# Adafruit_Metro_M0_Express.net
KiCad netlist of a schematic drawn in EAGLE
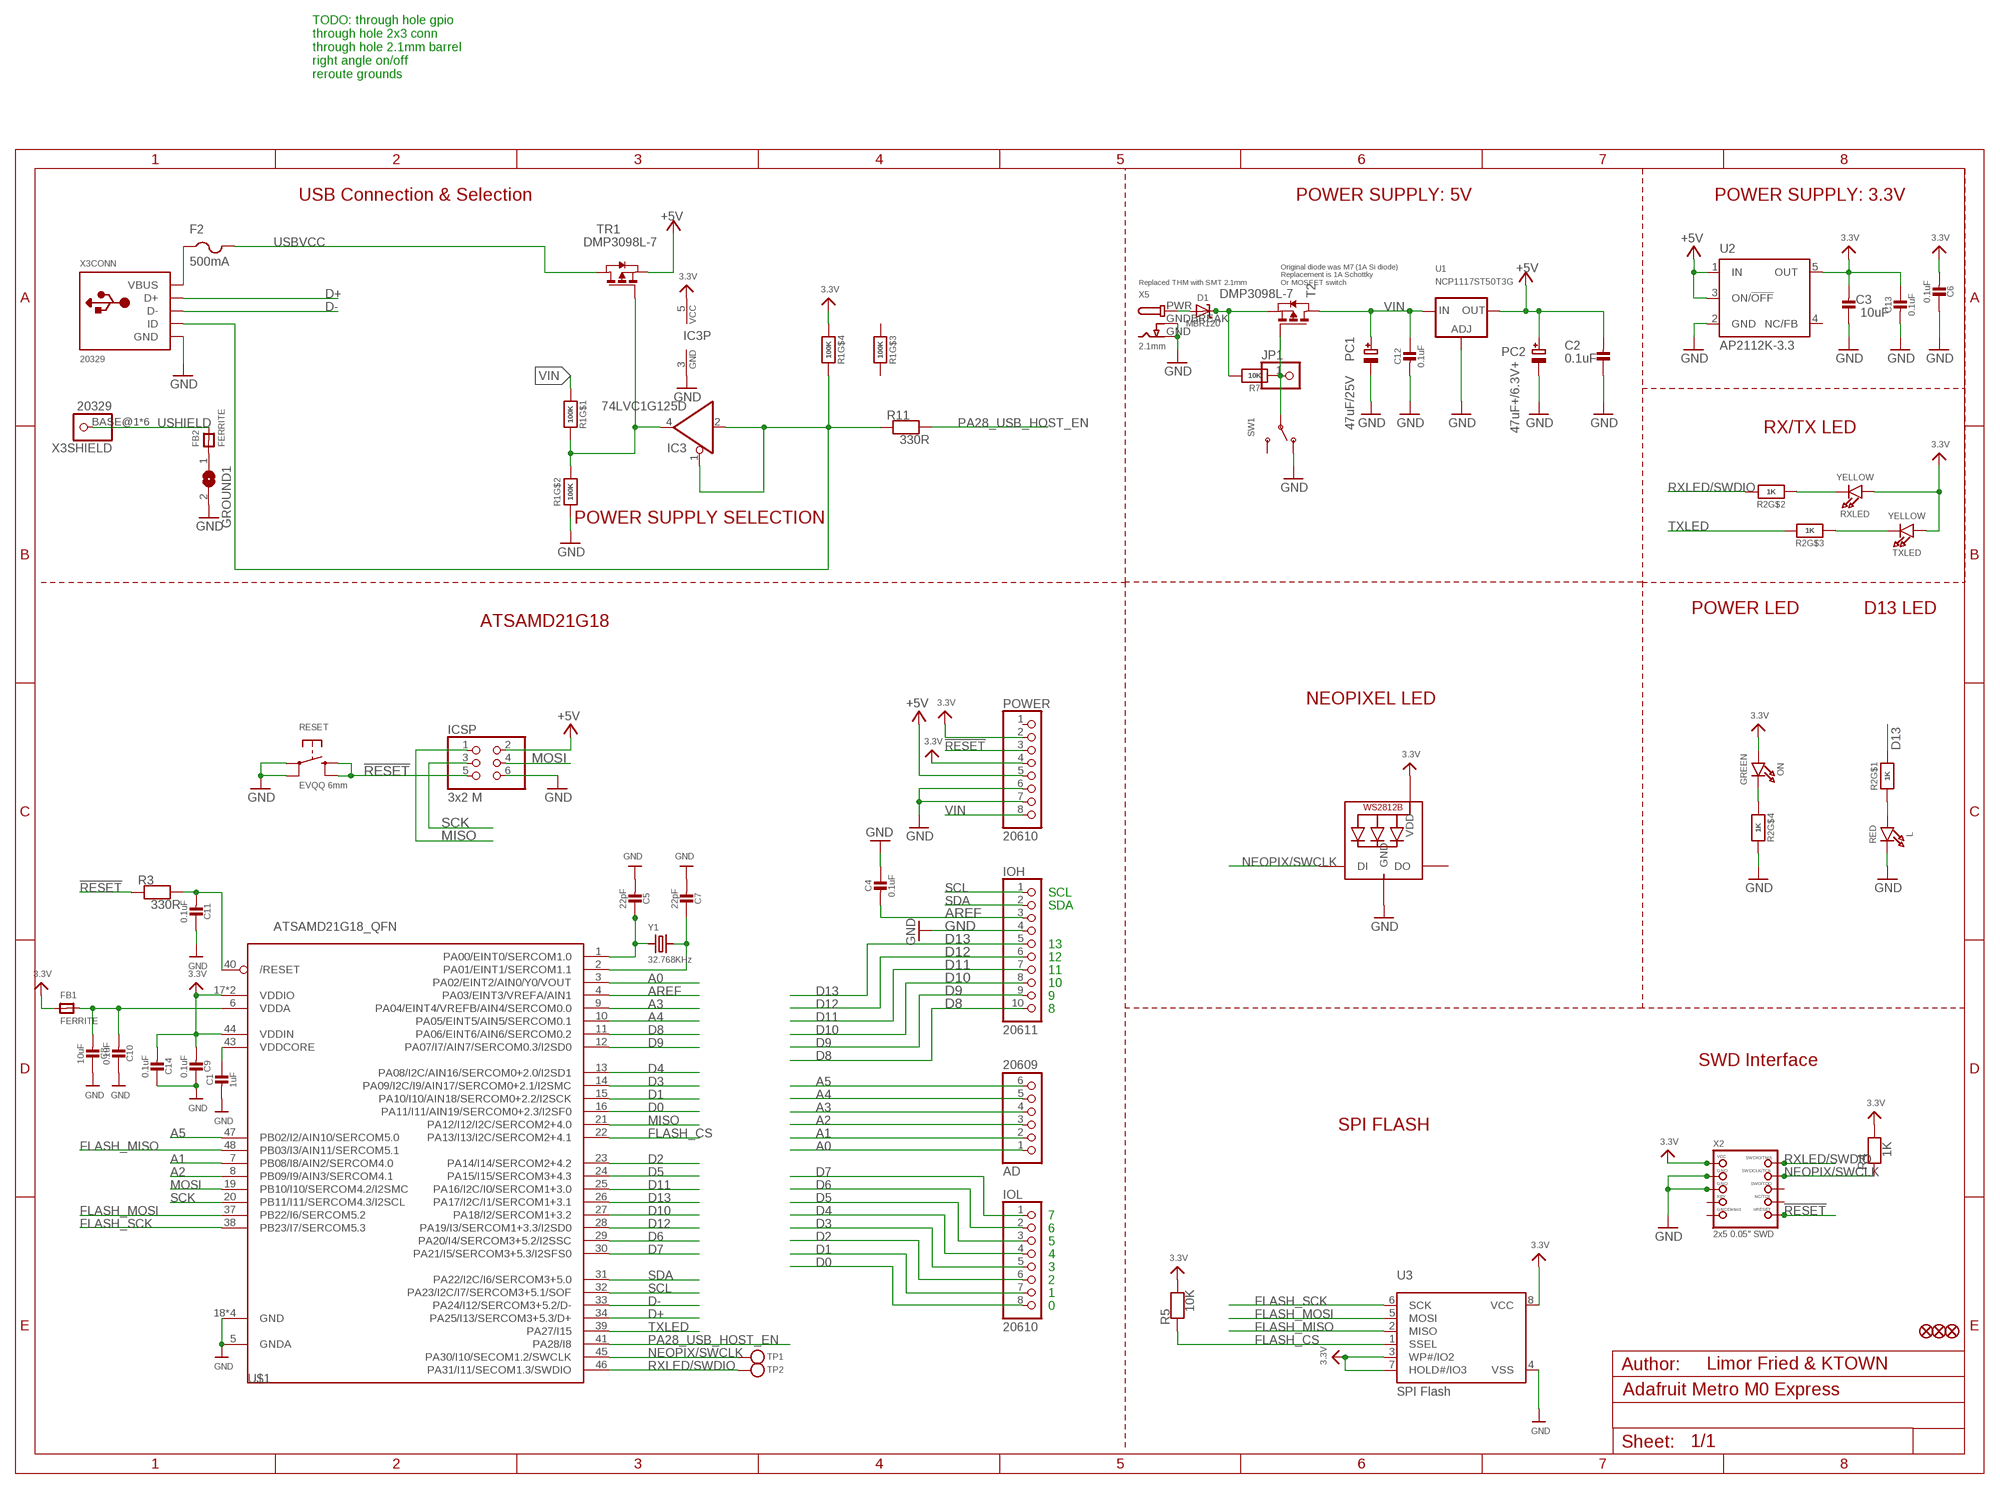
[diagram p0: schematic, sheet 1]

(export (version "E")
  (design (tool "Eeschema 10.0.6"))
  (components
    (comp (ref "AD")
      (value "20609")
      (footprint "eagle-import:1X06_OVALWAVE")
      (libsource (lib "eagle-import") (part "HEADER-1X6OVALWAVE"))
    )
    (comp (ref "C1")
      (value "1uF")
      (footprint "eagle-import:0805-NO")
      (libsource (lib "eagle-import") (part "CAP_CERAMIC0805-NOOUTLINE"))
    )
    (comp (ref "C2")
      (value "0.1uF")
      (footprint "eagle-import:0805-NO")
      (libsource (lib "eagle-import") (part "CAP_CERAMIC0805-NOOUTLINE"))
    )
    (comp (ref "C3")
      (value "10uF")
      (footprint "eagle-import:0805-NO")
      (libsource (lib "eagle-import") (part "CAP_CERAMIC0805-NOOUTLINE"))
    )
    (comp (ref "C4")
      (value "0.1uF")
      (footprint "eagle-import:0805-NO")
      (libsource (lib "eagle-import") (part "CAP_CERAMIC0805-NOOUTLINE"))
    )
    (comp (ref "C5")
      (value "22pF")
      (footprint "eagle-import:0805-NO")
      (libsource (lib "eagle-import") (part "CAP_CERAMIC0805-NOOUTLINE"))
    )
    (comp (ref "C6")
      (value "0.1uF")
      (footprint "eagle-import:0805-NO")
      (libsource (lib "eagle-import") (part "CAP_CERAMIC0805-NOOUTLINE"))
    )
    (comp (ref "C7")
      (value "22pF")
      (footprint "eagle-import:0805-NO")
      (libsource (lib "eagle-import") (part "CAP_CERAMIC0805-NOOUTLINE"))
    )
    (comp (ref "C8")
      (value "10uF")
      (footprint "eagle-import:0805-NO")
      (libsource (lib "eagle-import") (part "CAP_CERAMIC0805-NOOUTLINE"))
    )
    (comp (ref "C9")
      (value "0.1uF")
      (footprint "eagle-import:0805-NO")
      (libsource (lib "eagle-import") (part "CAP_CERAMIC0805-NOOUTLINE"))
    )
    (comp (ref "C10")
      (value "0.1uF")
      (footprint "eagle-import:0805-NO")
      (libsource (lib "eagle-import") (part "CAP_CERAMIC0805-NOOUTLINE"))
    )
    (comp (ref "C11")
      (value "0.1uF")
      (footprint "eagle-import:0805-NO")
      (libsource (lib "eagle-import") (part "CAP_CERAMIC0805-NOOUTLINE"))
    )
    (comp (ref "C12")
      (value "0.1uF")
      (footprint "eagle-import:0805-NO")
      (libsource (lib "eagle-import") (part "CAP_CERAMIC0805-NOOUTLINE"))
    )
    (comp (ref "C13")
      (value "0.1uF")
      (footprint "eagle-import:0805-NO")
      (libsource (lib "eagle-import") (part "CAP_CERAMIC0805-NOOUTLINE"))
    )
    (comp (ref "C14")
      (value "0.1uF")
      (footprint "eagle-import:0805-NO")
      (libsource (lib "eagle-import") (part "CAP_CERAMIC0805-NOOUTLINE"))
    )
    (comp (ref "D1")
      (value "MBR120")
      (footprint "eagle-import:SOD-123")
      (libsource (lib "eagle-import") (part "DIODE-SCHOTTKYSOD-123"))
    )
    (comp (ref "F2")
      (value "500mA")
      (footprint "eagle-import:R1206")
      (libsource (lib "eagle-import") (part "PTCFUSE-1206"))
    )
    (comp (ref "FB1")
      (value "FERRITE")
      (footprint "eagle-import:0805-NO")
      (libsource (lib "eagle-import") (part "FERRITE-0805NO"))
    )
    (comp (ref "FB2")
      (value "FERRITE")
      (footprint "eagle-import:0805-NO")
      (libsource (lib "eagle-import") (part "FERRITE-0805NO"))
    )
    (comp (ref "FD1")
      (value "FIDUCIAL_1MM")
      (footprint "eagle-import:FIDUCIAL_1MM")
      (libsource (lib "eagle-import") (part "FIDUCIAL_1MM"))
    )
    (comp (ref "FD2")
      (value "FIDUCIAL_1MM")
      (footprint "eagle-import:FIDUCIAL_1MM")
      (libsource (lib "eagle-import") (part "FIDUCIAL_1MM"))
    )
    (comp (ref "FD3")
      (value "FIDUCIAL_1MM")
      (footprint "eagle-import:FIDUCIAL_1MM")
      (libsource (lib "eagle-import") (part "FIDUCIAL_1MM"))
    )
    (comp (ref "GROUND1")
      (value "SJ")
      (footprint "eagle-import:SJ")
      (libsource (lib "eagle-import") (part "SJ"))
    )
    (comp (ref "IC3")
      (value "74LVC1G125D")
      (footprint "eagle-import:SOT23-5")
      (libsource (lib "eagle-import") (part "741G125DBVAHC"))
    )
    (comp (ref "ICSP")
      (value "3x2 M")
      (footprint "eagle-import:2X03_ROUND_70MIL")
      (libsource (lib "eagle-import") (part "HEADER-2X3"))
    )
    (comp (ref "IOH")
      (value "20611")
      (footprint "eagle-import:1X10_OVALWAVE")
      (libsource (lib "eagle-import") (part "HEADER-1X10OVALWAVE"))
    )
    (comp (ref "IOL")
      (value "20610")
      (footprint "eagle-import:1X08_OVALWAVE")
      (libsource (lib "eagle-import") (part "HEADER-1X8OVALWAVE"))
    )
    (comp (ref "JP1")
      (value "HEADER-1X1ROUND")
      (footprint "eagle-import:1X01_ROUND")
      (libsource (lib "eagle-import") (part "HEADER-1X1ROUND"))
    )
    (comp (ref "L")
      (value "RED")
      (footprint "eagle-import:CHIPLED_0805_NOOUTLINE")
      (libsource (lib "eagle-import") (part "LED0805_NOOUTLINE"))
    )
    (comp (ref "LED1")
      (value "WS2812B3535")
      (footprint "eagle-import:LED3535")
      (libsource (lib "eagle-import") (part "WS2812B3535"))
    )
    (comp (ref "ON")
      (value "GREEN")
      (footprint "eagle-import:CHIPLED_0805_NOOUTLINE")
      (libsource (lib "eagle-import") (part "LED0805_NOOUTLINE"))
    )
    (comp (ref "PC1")
      (value "47uF/25V")
      (footprint "eagle-import:PANASONIC_D")
      (libsource (lib "eagle-import") (part "CAP_ELECTROLYTICPANASONIC_D"))
    )
    (comp (ref "PC2")
      (value "47uF+/6.3V+")
      (footprint "eagle-import:PANASONIC_D")
      (libsource (lib "eagle-import") (part "CAP_ELECTROLYTICPANASONIC_D"))
    )
    (comp (ref "POWER")
      (value "20610")
      (footprint "eagle-import:1X08_OVALWAVE")
      (libsource (lib "eagle-import") (part "HEADER-1X8OVALWAVE"))
    )
    (comp (ref "R1")
      (value "100K")
      (footprint "eagle-import:RESPACK_4X0603")
      (libsource (lib "eagle-import") (part "RESISTOR_4PACK"))
    )
    (comp (ref "R2")
      (value "1K")
      (footprint "eagle-import:RESPACK_4X0603")
      (libsource (lib "eagle-import") (part "RESISTOR_4PACK"))
    )
    (comp (ref "R3")
      (value "330R")
      (footprint "eagle-import:0805-NO")
      (libsource (lib "eagle-import") (part "RESISTOR0805_NOOUTLINE"))
    )
    (comp (ref "R4")
      (value "1K")
      (footprint "eagle-import:0805-NO")
      (libsource (lib "eagle-import") (part "RESISTOR0805_NOOUTLINE"))
    )
    (comp (ref "R5")
      (value "10K")
      (footprint "eagle-import:0805-NO")
      (libsource (lib "eagle-import") (part "RESISTOR0805_NOOUTLINE"))
    )
    (comp (ref "R7")
      (value "10K")
      (footprint "eagle-import:0805-NO")
      (libsource (lib "eagle-import") (part "RESISTOR0805_NOOUTLINE"))
    )
    (comp (ref "R11")
      (value "330R")
      (footprint "eagle-import:0805-NO")
      (libsource (lib "eagle-import") (part "RESISTOR0805_NOOUTLINE"))
    )
    (comp (ref "RESET")
      (value "EVQQ 6mm")
      (footprint "eagle-import:EVQ-Q2")
      (libsource (lib "eagle-import") (part "SWITCH_TACT_SMT"))
    )
    (comp (ref "RXLED")
      (value "YELLOW")
      (footprint "eagle-import:CHIPLED_0805_NOOUTLINE")
      (libsource (lib "eagle-import") (part "LED0805_NOOUTLINE"))
    )
    (comp (ref "SW1")
      (value "SWITCH_SPDT")
      (footprint "eagle-import:SPDT_SMT_SSSS811101")
      (libsource (lib "eagle-import") (part "SWITCH_SPDT"))
    )
    (comp (ref "T2")
      (value "DMP3098L-7")
      (footprint "eagle-import:SOT-23")
      (libsource (lib "eagle-import") (part "PMOSSOT23"))
    )
    (comp (ref "TP1")
      (value "TESTPOINTROUND1.5MM")
      (footprint "eagle-import:TESTPOINT_ROUND_1.5MM")
      (libsource (lib "eagle-import") (part "TESTPOINTROUND1.5MM"))
    )
    (comp (ref "TP2")
      (value "TESTPOINTROUND1.5MM")
      (footprint "eagle-import:TESTPOINT_ROUND_1.5MM")
      (libsource (lib "eagle-import") (part "TESTPOINTROUND1.5MM"))
    )
    (comp (ref "TR1")
      (value "DMP3098L-7")
      (footprint "eagle-import:SOT-23")
      (fields (field (name "PART_NUMBER") "PMV48XP"))
      (libsource (lib "eagle-import") (part "0297_PMV48XP"))
    )
    (comp (ref "TXLED")
      (value "YELLOW")
      (footprint "eagle-import:CHIPLED_0805_NOOUTLINE")
      (libsource (lib "eagle-import") (part "LED0805_NOOUTLINE"))
    )
    (comp (ref "U$1")
      (value "ATSAMD21G18_QFN")
      (footprint "eagle-import:TQFN48_7MM")
      (libsource (lib "eagle-import") (part "ATSAMD21J_QFN"))
    )
    (comp (ref "U1")
      (value "NCP1117ST50T3G")
      (footprint "eagle-import:SOT223-R")
      (libsource (lib "eagle-import") (part "LM1117SOT223-REFLOW"))
    )
    (comp (ref "U2")
      (value "AP2112K-3.3")
      (footprint "eagle-import:SOT23-DBV")
      (libsource (lib "eagle-import") (part "LP2985-XXDBVR33"))
    )
    (comp (ref "U3")
      (value "SPI Flash")
      (footprint "eagle-import:SOIC8_208MIL")
      (libsource (lib "eagle-import") (part "SPIFLASH_SOIC8208MIL"))
    )
    (comp (ref "X2")
      (value "2x5 0.05\" SWD")
      (footprint "eagle-import:2X05_1.27MM_BOX_POSTS")
      (libsource (lib "eagle-import") (part "JTAG-CORTEXBOXPOSTS"))
    )
    (comp (ref "X3")
      (value "20329")
      (footprint "eagle-import:4UCONN_20329_V2")
      (libsource (lib "eagle-import") (part "USB_W_SHIELD_V2"))
    )
    (comp (ref "X5")
      (value "2.1mm")
      (footprint "eagle-import:DCJACK_2MM_PTH")
      (libsource (lib "eagle-import") (part "DCBARRELPTH"))
    )
    (comp (ref "Y1")
      (value "32.768KHz")
      (footprint "eagle-import:CRYSTAL_8X3.8")
      (libsource (lib "eagle-import") (part "CRYSTAL8.0X3.8"))
    )
  )
  (nets
    (net (code "1") (name "+5V") (class "Default")
      (node (ref "C2") (pin "2") (pinfunction "2_2") (pintype "passive"))
      (node (ref "ICSP") (pin "2") (pinfunction "2_2") (pintype "passive"))
      (node (ref "PC2") (pin "+") (pinfunction "+_+") (pintype "passive"))
      (node (ref "POWER") (pin "5") (pinfunction "5_5") (pintype "passive"))
      (node (ref "TR1") (pin "2") (pinfunction "S_2") (pintype "passive"))
      (node (ref "U1") (pin "2") (pinfunction "OUT_2") (pintype "passive"))
      (node (ref "U1") (pin "4") (pinfunction "OUT_4") (pintype "passive"))
      (node (ref "U2") (pin "1") (pinfunction "IN_1") (pintype "input"))
      (node (ref "U2") (pin "3") (pinfunction "ON/~{OFF}_3") (pintype "input"))
    )
    (net (code "2") (name "/A0") (class "Default")
      (node (ref "AD") (pin "1") (pinfunction "1_1") (pintype "passive"))
      (node (ref "U$1") (pin "3") (pinfunction "PA02/EINT2/AIN0/Y0/VOUT_3") (pintype "bidirectional"))
    )
    (net (code "3") (name "/A1") (class "Default")
      (node (ref "AD") (pin "2") (pinfunction "2_2") (pintype "passive"))
      (node (ref "U$1") (pin "7") (pinfunction "PB08/I8/AIN2/SERCOM4.0_7") (pintype "bidirectional"))
    )
    (net (code "4") (name "/A2") (class "Default")
      (node (ref "AD") (pin "3") (pinfunction "3_3") (pintype "passive"))
      (node (ref "U$1") (pin "8") (pinfunction "PB09/I9/AIN3/SERCOM4.1_8") (pintype "bidirectional"))
    )
    (net (code "5") (name "/A3") (class "Default")
      (node (ref "AD") (pin "4") (pinfunction "4_4") (pintype "passive"))
      (node (ref "U$1") (pin "9") (pinfunction "PA04/EINT4/VREFB/AIN4/SERCOM0.0_9") (pintype "bidirectional"))
    )
    (net (code "6") (name "/A4") (class "Default")
      (node (ref "AD") (pin "5") (pinfunction "5_5") (pintype "passive"))
      (node (ref "U$1") (pin "10") (pinfunction "PA05/EINT5/AIN5/SERCOM0.1_10") (pintype "bidirectional"))
    )
    (net (code "7") (name "/A5") (class "Default")
      (node (ref "AD") (pin "6") (pinfunction "6_6") (pintype "passive"))
      (node (ref "U$1") (pin "47") (pinfunction "PB02/I2/AIN10/SERCOM5.0_47") (pintype "bidirectional"))
    )
    (net (code "8") (name "/AREF") (class "Default")
      (node (ref "C4") (pin "2") (pinfunction "2_2") (pintype "passive"))
      (node (ref "IOH") (pin "3") (pinfunction "3_3") (pintype "passive"))
      (node (ref "U$1") (pin "4") (pinfunction "PA03/EINT3/VREFA/AIN1_4") (pintype "bidirectional"))
    )
    (net (code "9") (name "/D+") (class "Default")
      (node (ref "U$1") (pin "34") (pinfunction "PA25/I13/SERCOM3+5.3/D+_34") (pintype "bidirectional"))
      (node (ref "X3") (pin "D+") (pinfunction "D+_D+") (pintype "bidirectional"))
    )
    (net (code "10") (name "/D-") (class "Default")
      (node (ref "U$1") (pin "33") (pinfunction "PA24/I12/SERCOM3+5.2/D-_33") (pintype "bidirectional"))
      (node (ref "X3") (pin "D-") (pinfunction "D-_D-") (pintype "bidirectional"))
    )
    (net (code "11") (name "/D0") (class "Default")
      (node (ref "IOL") (pin "8") (pinfunction "8_8") (pintype "passive"))
      (node (ref "U$1") (pin "16") (pinfunction "PA11/I11/AIN19/SERCOM0+2.3/I2SF0_16") (pintype "bidirectional"))
    )
    (net (code "12") (name "/D1") (class "Default")
      (node (ref "IOL") (pin "7") (pinfunction "7_7") (pintype "passive"))
      (node (ref "U$1") (pin "15") (pinfunction "PA10/I10/AIN18/SERCOM0+2.2/I2SCK_15") (pintype "bidirectional"))
    )
    (net (code "13") (name "/D2") (class "Default")
      (node (ref "IOL") (pin "6") (pinfunction "6_6") (pintype "passive"))
      (node (ref "U$1") (pin "23") (pinfunction "PA14/I14/SERCOM2+4.2_23") (pintype "bidirectional"))
    )
    (net (code "14") (name "/D3") (class "Default")
      (node (ref "IOL") (pin "5") (pinfunction "5_5") (pintype "passive"))
      (node (ref "U$1") (pin "14") (pinfunction "PA09/I2C/I9/AIN17/SERCOM0+2.1/I2SMC_14") (pintype "bidirectional"))
    )
    (net (code "15") (name "/D4") (class "Default")
      (node (ref "IOL") (pin "4") (pinfunction "4_4") (pintype "passive"))
      (node (ref "U$1") (pin "13") (pinfunction "PA08/I2C/AIN16/SERCOM0+2.0/I2SD1_13") (pintype "bidirectional"))
    )
    (net (code "16") (name "/D5") (class "Default")
      (node (ref "IOL") (pin "3") (pinfunction "3_3") (pintype "passive"))
      (node (ref "U$1") (pin "24") (pinfunction "PA15/I15/SERCOM3+4.3_24") (pintype "bidirectional"))
    )
    (net (code "17") (name "/D6") (class "Default")
      (node (ref "IOL") (pin "2") (pinfunction "2_2") (pintype "passive"))
      (node (ref "U$1") (pin "29") (pinfunction "PA20/I4/SERCOM3+5.2/I2SSC_29") (pintype "bidirectional"))
    )
    (net (code "18") (name "/D7") (class "Default")
      (node (ref "IOL") (pin "1") (pinfunction "1_1") (pintype "passive"))
      (node (ref "U$1") (pin "30") (pinfunction "PA21/I5/SERCOM3+5.3/I2SFS0_30") (pintype "bidirectional"))
    )
    (net (code "19") (name "/D8") (class "Default")
      (node (ref "IOH") (pin "10") (pinfunction "10_10") (pintype "passive"))
      (node (ref "U$1") (pin "11") (pinfunction "PA06/EINT6/AIN6/SERCOM0.2_11") (pintype "bidirectional"))
    )
    (net (code "20") (name "/D9") (class "Default")
      (node (ref "IOH") (pin "9") (pinfunction "9_9") (pintype "passive"))
      (node (ref "U$1") (pin "12") (pinfunction "PA07/I7/AIN7/SERCOM0.3/I2SD0_12") (pintype "bidirectional"))
    )
    (net (code "21") (name "/D10") (class "Default")
      (node (ref "IOH") (pin "8") (pinfunction "8_8") (pintype "passive"))
      (node (ref "U$1") (pin "27") (pinfunction "PA18/I2/SERCOM1+3.2_27") (pintype "bidirectional"))
    )
    (net (code "22") (name "/D11") (class "Default")
      (node (ref "IOH") (pin "7") (pinfunction "7_7") (pintype "passive"))
      (node (ref "U$1") (pin "25") (pinfunction "PA16/I2C/I0/SERCOM1+3.0_25") (pintype "bidirectional"))
    )
    (net (code "23") (name "/D12") (class "Default")
      (node (ref "IOH") (pin "6") (pinfunction "6_6") (pintype "passive"))
      (node (ref "U$1") (pin "28") (pinfunction "PA19/I3/SERCOM1+3.3/I2SD0_28") (pintype "bidirectional"))
    )
    (net (code "24") (name "/D13") (class "Default")
      (node (ref "IOH") (pin "5") (pinfunction "5_5") (pintype "passive"))
      (node (ref "R2") (pin "8") (pinfunction "2_8") (pintype "passive"))
      (node (ref "U$1") (pin "26") (pinfunction "PA17/I2C/I1/SERCOM1+3.1_26") (pintype "bidirectional"))
    )
    (net (code "25") (name "/FLASH_CS") (class "Default")
      (node (ref "R5") (pin "1") (pinfunction "1_1") (pintype "passive"))
      (node (ref "U$1") (pin "22") (pinfunction "PA13/I13/I2C/SERCOM2+4.1_22") (pintype "bidirectional"))
      (node (ref "U3") (pin "1") (pinfunction "SSEL_1") (pintype "bidirectional"))
    )
    (net (code "26") (name "/FLASH_MISO") (class "Default")
      (node (ref "U$1") (pin "48") (pinfunction "PB03/I3/AIN11/SERCOM5.1_48") (pintype "bidirectional"))
      (node (ref "U3") (pin "2") (pinfunction "MISO_2") (pintype "bidirectional"))
    )
    (net (code "27") (name "/FLASH_MOSI") (class "Default")
      (node (ref "U$1") (pin "37") (pinfunction "PB22/I6/SERCOM5.2_37") (pintype "bidirectional"))
      (node (ref "U3") (pin "5") (pinfunction "MOSI_5") (pintype "bidirectional"))
    )
    (net (code "28") (name "/FLASH_SCK") (class "Default")
      (node (ref "U$1") (pin "38") (pinfunction "PB23/I7/SERCOM5.3_38") (pintype "bidirectional"))
      (node (ref "U3") (pin "6") (pinfunction "SCK_6") (pintype "bidirectional"))
    )
    (net (code "29") (name "/MISO") (class "Default")
      (node (ref "ICSP") (pin "1") (pinfunction "1_1") (pintype "passive"))
      (node (ref "U$1") (pin "21") (pinfunction "PA12/I12/I2C/SERCOM2+4.0_21") (pintype "bidirectional"))
    )
    (net (code "30") (name "/MOSI") (class "Default")
      (node (ref "ICSP") (pin "4") (pinfunction "4_4") (pintype "passive"))
      (node (ref "U$1") (pin "19") (pinfunction "PB10/I10/SERCOM4.2/I2SMC_19") (pintype "bidirectional"))
    )
    (net (code "31") (name "/NEOPIX{slash}SWCLK") (class "Default")
      (node (ref "LED1") (pin "1") (pinfunction "DI_1") (pintype "input"))
      (node (ref "R4") (pin "1") (pinfunction "1_1") (pintype "passive"))
      (node (ref "TP1") (pin "P$1") (pinfunction "P$1_P$1") (pintype "bidirectional"))
      (node (ref "U$1") (pin "45") (pinfunction "PA30/I10/SECOM1.2/SWCLK_45") (pintype "bidirectional"))
      (node (ref "X2") (pin "4") (pinfunction "SWDCLK_4") (pintype "bidirectional"))
    )
    (net (code "32") (name "/PA28_USB_HOST_EN") (class "Default")
      (node (ref "R11") (pin "2") (pinfunction "2_2") (pintype "passive"))
      (node (ref "U$1") (pin "41") (pinfunction "PA28/I8_41") (pintype "bidirectional"))
    )
    (net (code "33") (name "/RXLED{slash}SWDIO") (class "Default")
      (node (ref "R2") (pin "7") (pinfunction "2_7") (pintype "passive"))
      (node (ref "TP2") (pin "P$1") (pinfunction "P$1_P$1") (pintype "bidirectional"))
      (node (ref "U$1") (pin "46") (pinfunction "PA31/I11/SECOM1.3/SWDIO_46") (pintype "bidirectional"))
      (node (ref "X2") (pin "2") (pinfunction "SWDIO_2") (pintype "bidirectional"))
    )
    (net (code "34") (name "/SCK") (class "Default")
      (node (ref "ICSP") (pin "3") (pinfunction "3_3") (pintype "passive"))
      (node (ref "U$1") (pin "20") (pinfunction "PB11/I11/SERCOM4.3/I2SCL_20") (pintype "bidirectional"))
    )
    (net (code "35") (name "/SCL") (class "Default")
      (node (ref "IOH") (pin "1") (pinfunction "1_1") (pintype "passive"))
      (node (ref "U$1") (pin "32") (pinfunction "PA23/I2C/I7/SERCOM3+5.1/SOF_32") (pintype "bidirectional"))
    )
    (net (code "36") (name "/SDA") (class "Default")
      (node (ref "IOH") (pin "2") (pinfunction "2_2") (pintype "passive"))
      (node (ref "U$1") (pin "31") (pinfunction "PA22/I2C/I6/SERCOM3+5.0_31") (pintype "bidirectional"))
    )
    (net (code "37") (name "/TXLED") (class "Default")
      (node (ref "R2") (pin "6") (pinfunction "2_6") (pintype "passive"))
      (node (ref "U$1") (pin "39") (pinfunction "PA27/I15_39") (pintype "bidirectional"))
    )
    (net (code "38") (name "/USBVCC") (class "Default")
      (node (ref "F2") (pin "2") (pinfunction "2_2") (pintype "passive"))
      (node (ref "TR1") (pin "1") (pinfunction "D_1") (pintype "passive"))
    )
    (net (code "39") (name "/USHIELD") (class "Default")
      (node (ref "FB2") (pin "2") (pinfunction "P$2_2") (pintype "passive"))
      (node (ref "X3") (pin "BASE@1") (pinfunction "1_BASE@1") (pintype "passive"))
      (node (ref "X3") (pin "BASE@2") (pinfunction "1_BASE@2") (pintype "passive"))
      (node (ref "X3") (pin "SPRT@1") (pinfunction "1_SPRT@1") (pintype "passive"))
      (node (ref "X3") (pin "SPRT@2") (pinfunction "1_SPRT@2") (pintype "passive"))
      (node (ref "X3") (pin "SPRT@3") (pinfunction "1_SPRT@3") (pintype "passive"))
      (node (ref "X3") (pin "SPRT@4") (pinfunction "1_SPRT@4") (pintype "passive"))
    )
    (net (code "40") (name "/~{RESET}") (class "Default")
      (node (ref "ICSP") (pin "5") (pinfunction "5_5") (pintype "passive"))
      (node (ref "POWER") (pin "3") (pinfunction "3_3") (pintype "passive"))
      (node (ref "R3") (pin "1") (pinfunction "1_1") (pintype "passive"))
      (node (ref "RESET") (pin "B") (pinfunction "S_B") (pintype "passive"))
      (node (ref "RESET") (pin "B'") (pinfunction "S1_B'") (pintype "passive"))
      (node (ref "X2") (pin "10") (pinfunction "NRESET_10") (pintype "bidirectional"))
    )
    (net (code "41") (name "3.3V") (class "Default")
      (node (ref "C13") (pin "1") (pinfunction "1_1") (pintype "passive"))
      (node (ref "C14") (pin "2") (pinfunction "2_2") (pintype "passive"))
      (node (ref "C3") (pin "2") (pinfunction "2_2") (pintype "passive"))
      (node (ref "C6") (pin "2") (pinfunction "2_2") (pintype "passive"))
      (node (ref "C9") (pin "2") (pinfunction "2_2") (pintype "passive"))
      (node (ref "FB1") (pin "1") (pinfunction "P$1_1") (pintype "passive"))
      (node (ref "IC3") (pin "5") (pinfunction "VCC_5") (pintype "power_in"))
      (node (ref "LED1") (pin "2") (pinfunction "VDD_2") (pintype "power_in"))
      (node (ref "ON") (pin "A") (pinfunction "A_A") (pintype "passive"))
      (node (ref "POWER") (pin "2") (pinfunction "2_2") (pintype "passive"))
      (node (ref "POWER") (pin "4") (pinfunction "4_4") (pintype "passive"))
      (node (ref "R1") (pin "4") (pinfunction "1_4") (pintype "passive"))
      (node (ref "R4") (pin "2") (pinfunction "2_2") (pintype "passive"))
      (node (ref "R5") (pin "2") (pinfunction "2_2") (pintype "passive"))
      (node (ref "RXLED") (pin "A") (pinfunction "A_A") (pintype "passive"))
      (node (ref "TXLED") (pin "A") (pinfunction "A_A") (pintype "passive"))
      (node (ref "U$1") (pin "17") (pinfunction "VDDIO_17") (pintype "power_in"))
      (node (ref "U$1") (pin "36") (pinfunction "VDDIO_36") (pintype "power_in"))
      (node (ref "U$1") (pin "44") (pinfunction "VDDIN_44") (pintype "power_in"))
      (node (ref "U2") (pin "5") (pinfunction "OUT_5") (pintype "passive"))
      (node (ref "U3") (pin "3") (pinfunction "WP#/IO2_3") (pintype "bidirectional"))
      (node (ref "U3") (pin "7") (pinfunction "HOLD#/IO3_7") (pintype "bidirectional"))
      (node (ref "U3") (pin "8") (pinfunction "VCC_8") (pintype "bidirectional"))
      (node (ref "X2") (pin "1") (pinfunction "VCC_1") (pintype "power_in"))
    )
    (net (code "42") (name "GND") (class "Default")
      (node (ref "C1") (pin "2") (pinfunction "2_2") (pintype "passive"))
      (node (ref "C10") (pin "1") (pinfunction "1_1") (pintype "passive"))
      (node (ref "C11") (pin "1") (pinfunction "1_1") (pintype "passive"))
      (node (ref "C12") (pin "2") (pinfunction "2_2") (pintype "passive"))
      (node (ref "C13") (pin "2") (pinfunction "2_2") (pintype "passive"))
      (node (ref "C14") (pin "1") (pinfunction "1_1") (pintype "passive"))
      (node (ref "C2") (pin "1") (pinfunction "1_1") (pintype "passive"))
      (node (ref "C3") (pin "1") (pinfunction "1_1") (pintype "passive"))
      (node (ref "C4") (pin "1") (pinfunction "1_1") (pintype "passive"))
      (node (ref "C5") (pin "2") (pinfunction "2_2") (pintype "passive"))
      (node (ref "C6") (pin "1") (pinfunction "1_1") (pintype "passive"))
      (node (ref "C7") (pin "2") (pinfunction "2_2") (pintype "passive"))
      (node (ref "C8") (pin "1") (pinfunction "1_1") (pintype "passive"))
      (node (ref "C9") (pin "1") (pinfunction "1_1") (pintype "passive"))
      (node (ref "GROUND1") (pin "2") (pinfunction "2_2") (pintype "passive"))
      (node (ref "IC3") (pin "3") (pinfunction "GND_3") (pintype "power_in"))
      (node (ref "ICSP") (pin "6") (pinfunction "6_6") (pintype "passive"))
      (node (ref "IOH") (pin "4") (pinfunction "4_4") (pintype "passive"))
      (node (ref "L") (pin "C") (pinfunction "C_C") (pintype "passive"))
      (node (ref "LED1") (pin "4") (pinfunction "GND_4") (pintype "power_in"))
      (node (ref "PC1") (pin "-") (pinfunction "-_-") (pintype "passive"))
      (node (ref "PC2") (pin "-") (pinfunction "-_-") (pintype "passive"))
      (node (ref "POWER") (pin "6") (pinfunction "6_6") (pintype "passive"))
      (node (ref "POWER") (pin "7") (pinfunction "7_7") (pintype "passive"))
      (node (ref "R1") (pin "2") (pinfunction "1_2") (pintype "passive"))
      (node (ref "R2") (pin "5") (pinfunction "2_5") (pintype "passive"))
      (node (ref "RESET") (pin "A") (pinfunction "P_A") (pintype "passive"))
      (node (ref "RESET") (pin "A'") (pinfunction "P1_A'") (pintype "passive"))
      (node (ref "SW1") (pin "A") (pinfunction "O_A") (pintype "passive"))
      (node (ref "U$1") (pin "18") (pinfunction "GND_18") (pintype "power_in"))
      (node (ref "U$1") (pin "35") (pinfunction "GND_35") (pintype "power_in"))
      (node (ref "U$1") (pin "42") (pinfunction "GND_42") (pintype "power_in"))
      (node (ref "U$1") (pin "5") (pinfunction "GNDA_5") (pintype "power_in"))
      (node (ref "U$1") (pin "THERMAL") (pinfunction "GND_THERMAL") (pintype "power_in"))
      (node (ref "U1") (pin "1") (pinfunction "ADJ_1") (pintype "input"))
      (node (ref "U2") (pin "2") (pinfunction "GND_2") (pintype "power_in"))
      (node (ref "U3") (pin "4") (pinfunction "VSS_4") (pintype "bidirectional"))
      (node (ref "X2") (pin "3") (pinfunction "GND_3") (pintype "power_in"))
      (node (ref "X2") (pin "5") (pinfunction "GND_5") (pintype "power_in"))
      (node (ref "X3") (pin "GND") (pinfunction "GND_GND") (pintype "power_in"))
      (node (ref "X5") (pin "GND") (pinfunction "GND_GND") (pintype "power_in"))
      (node (ref "X5") (pin "GNDBREAK") (pinfunction "GNDBREAK_GNDBREAK") (pintype "power_in"))
    )
    (net (code "43") (name "Net-(D1-PadA)") (class "Default")
      (node (ref "D1") (pin "A") (pinfunction "A_A") (pintype "passive"))
      (node (ref "X5") (pin "PWR") (pinfunction "PWR_PWR") (pintype "power_in"))
    )
    (net (code "44") (name "Net-(F2-Pad1)") (class "Default")
      (node (ref "F2") (pin "1") (pinfunction "1_1") (pintype "passive"))
      (node (ref "X3") (pin "VBUS") (pinfunction "VBUS_VBUS") (pintype "power_in"))
    )
    (net (code "45") (name "Net-(FB1-P$2)") (class "Default")
      (node (ref "C10") (pin "2") (pinfunction "2_2") (pintype "passive"))
      (node (ref "C8") (pin "2") (pinfunction "2_2") (pintype "passive"))
      (node (ref "FB1") (pin "2") (pinfunction "P$2_2") (pintype "passive"))
      (node (ref "U$1") (pin "6") (pinfunction "VDDA_6") (pintype "power_in"))
    )
    (net (code "46") (name "Net-(FB2-P$1)") (class "Default")
      (node (ref "FB2") (pin "1") (pinfunction "P$1_1") (pintype "passive"))
      (node (ref "GROUND1") (pin "1") (pinfunction "1_1") (pintype "passive"))
    )
    (net (code "47") (name "Net-(IC3A-I)") (class "Default")
      (node (ref "IC3") (pin "1") (pinfunction "OE_1") (pintype "input"))
      (node (ref "IC3") (pin "2") (pinfunction "I_2") (pintype "input"))
      (node (ref "R1") (pin "5") (pinfunction "2_5") (pintype "passive"))
      (node (ref "R11") (pin "1") (pinfunction "1_1") (pintype "passive"))
      (node (ref "X3") (pin "ID") (pinfunction "ID_ID") (pintype "bidirectional"))
    )
    (net (code "48") (name "Net-(IC3A-O)") (class "Default")
      (node (ref "IC3") (pin "4") (pinfunction "O_4") (pintype "tri_state"))
      (node (ref "R1") (pin "7") (pinfunction "2_7") (pintype "passive"))
      (node (ref "R1") (pin "8") (pinfunction "2_8") (pintype "passive"))
      (node (ref "TR1") (pin "3") (pinfunction "G_3") (pintype "passive"))
    )
    (net (code "49") (name "Net-(L-PadA)") (class "Default")
      (node (ref "L") (pin "A") (pinfunction "A_A") (pintype "passive"))
      (node (ref "R2") (pin "1") (pinfunction "1_1") (pintype "passive"))
    )
    (net (code "50") (name "Net-(R2B-1)") (class "Default")
      (node (ref "R2") (pin "2") (pinfunction "1_2") (pintype "passive"))
      (node (ref "RXLED") (pin "C") (pinfunction "C_C") (pintype "passive"))
    )
    (net (code "51") (name "Net-(R2C-1)") (class "Default")
      (node (ref "R2") (pin "3") (pinfunction "1_3") (pintype "passive"))
      (node (ref "TXLED") (pin "C") (pinfunction "C_C") (pintype "passive"))
    )
    (net (code "52") (name "Net-(R2D-1)") (class "Default")
      (node (ref "ON") (pin "C") (pinfunction "C_C") (pintype "passive"))
      (node (ref "R2") (pin "4") (pinfunction "1_4") (pintype "passive"))
    )
    (net (code "53") (name "Net-(SW1-P)") (class "Default")
      (node (ref "JP1") (pin "1") (pinfunction "1_1") (pintype "passive"))
      (node (ref "R7") (pin "1") (pinfunction "1_1") (pintype "passive"))
      (node (ref "SW1") (pin "B") (pinfunction "P_B") (pintype "passive"))
      (node (ref "T2") (pin "3") (pinfunction "G_3") (pintype "passive"))
    )
    (net (code "54") (name "Net-(T2-S)") (class "Default")
      (node (ref "D1") (pin "C") (pinfunction "C_C") (pintype "passive"))
      (node (ref "R7") (pin "2") (pinfunction "2_2") (pintype "passive"))
      (node (ref "T2") (pin "2") (pinfunction "S_2") (pintype "passive"))
    )
    (net (code "55") (name "Net-(U$1-PA00{slash}EINT0{slash}SERCOM1.0)") (class "Default")
      (node (ref "C5") (pin "1") (pinfunction "1_1") (pintype "passive"))
      (node (ref "U$1") (pin "1") (pinfunction "PA00/EINT0/SERCOM1.0_1") (pintype "bidirectional"))
      (node (ref "Y1") (pin "P$1") (pinfunction "1_P$1") (pintype "passive"))
    )
    (net (code "56") (name "Net-(U$1-PA01{slash}EINT1{slash}SERCOM1.1)") (class "Default")
      (node (ref "C7") (pin "1") (pinfunction "1_1") (pintype "passive"))
      (node (ref "U$1") (pin "2") (pinfunction "PA01/EINT1/SERCOM1.1_2") (pintype "bidirectional"))
      (node (ref "Y1") (pin "P$4") (pinfunction "2_P$4") (pintype "passive"))
    )
    (net (code "57") (name "Net-(U$1-VDDCORE)") (class "Default")
      (node (ref "C1") (pin "1") (pinfunction "1_1") (pintype "passive"))
      (node (ref "U$1") (pin "43") (pinfunction "VDDCORE_43") (pintype "power_in"))
    )
    (net (code "58") (name "Net-(U$1-{slash}RESET)") (class "Default")
      (node (ref "C11") (pin "2") (pinfunction "2_2") (pintype "passive"))
      (node (ref "R3") (pin "2") (pinfunction "2_2") (pintype "passive"))
      (node (ref "U$1") (pin "40") (pinfunction "/RESET_40") (pintype "bidirectional"))
    )
    (net (code "59") (name "VIN") (class "Default")
      (node (ref "C12") (pin "1") (pinfunction "1_1") (pintype "passive"))
      (node (ref "PC1") (pin "+") (pinfunction "+_+") (pintype "passive"))
      (node (ref "POWER") (pin "8") (pinfunction "8_8") (pintype "passive"))
      (node (ref "R1") (pin "1") (pinfunction "1_1") (pintype "passive"))
      (node (ref "T2") (pin "1") (pinfunction "D_1") (pintype "passive"))
      (node (ref "U1") (pin "3") (pinfunction "IN_3") (pintype "input"))
    )
    (net (code "60") (name "unconnected-(LED1-DO-Pad3)") (class "Default")
      (node (ref "LED1") (pin "3") (pinfunction "DO_3") (pintype "output"))
    )
    (net (code "61") (name "unconnected-(POWER-Pad1)") (class "Default")
      (node (ref "POWER") (pin "1") (pinfunction "1_1") (pintype "passive"))
    )
    (net (code "62") (name "unconnected-(R1C-1-Pad3)") (class "Default")
      (node (ref "R1") (pin "3") (pinfunction "1_3") (pintype "passive"))
    )
    (net (code "63") (name "unconnected-(R1C-2-Pad6)") (class "Default")
      (node (ref "R1") (pin "6") (pinfunction "2_6") (pintype "passive"))
    )
    (net (code "64") (name "unconnected-(SW1-S-PadC)") (class "Default")
      (node (ref "SW1") (pin "C") (pinfunction "S_C") (pintype "passive"))
    )
    (net (code "65") (name "unconnected-(U2-NC{slash}FB-Pad4)") (class "Default")
      (node (ref "U2") (pin "4") (pinfunction "NC/FB_4") (pintype "passive"))
    )
    (net (code "66") (name "unconnected-(X2-GNDDETECT-Pad9)") (class "Default")
      (node (ref "X2") (pin "9") (pinfunction "GNDDETECT_9") (pintype "bidirectional"))
    )
    (net (code "67") (name "unconnected-(X2-KEY-Pad7)") (class "Default")
      (node (ref "X2") (pin "7") (pinfunction "KEY_7") (pintype "bidirectional"))
    )
    (net (code "68") (name "unconnected-(X2-SWO-Pad6)") (class "Default")
      (node (ref "X2") (pin "6") (pinfunction "SWO_6") (pintype "bidirectional"))
    )
    (net (code "69") (name "unconnected-(X2-TDI-Pad8)") (class "Default")
      (node (ref "X2") (pin "8") (pinfunction "TDI_8") (pintype "bidirectional"))
    )
  )
)
